# project.net
KiCad netlist of a schematic drawn in Altium Designer
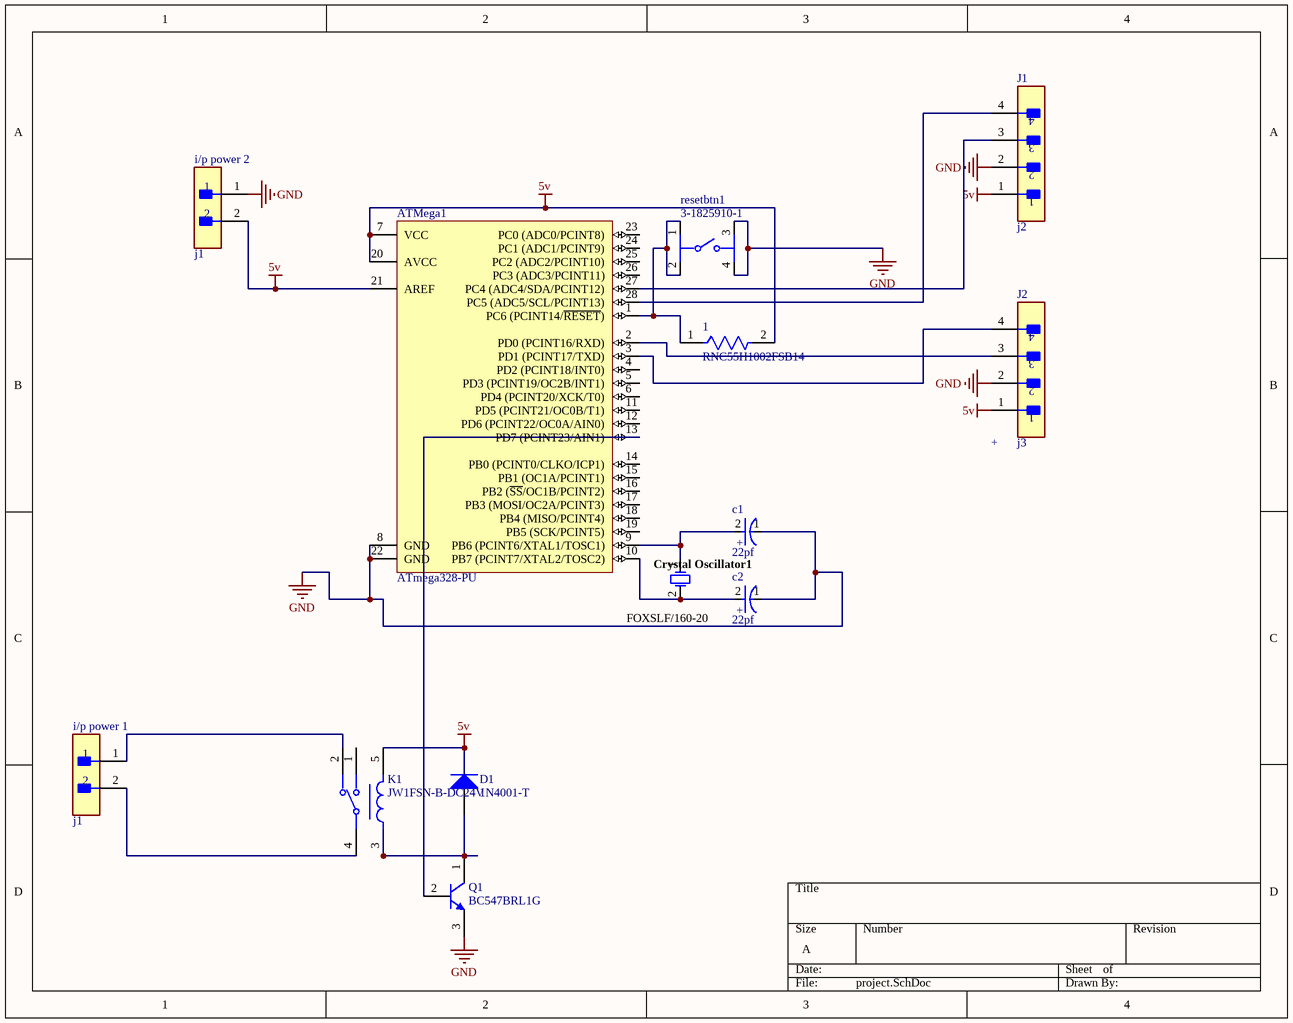
[diagram p0: project.SchDoc]

(export (version "E")
  (design (tool "Eeschema 10.0.6"))
  (components
    (comp (ref "1")
      (value "RNC55H1002FSB14")
      (footprint "FP-RNC55-MFG")
      (description "RES 10K OHM 1/8W 1% AXIAL")
      (fields
        (field (name "TOLERANCE") "1%")
        (field (name "OCTOPART") "https://octopart.com/rnc55h1002fs-vishay-40848808")
      )
      (libsource (lib "Altium Content Vault") (part "1029c3af85768c4190bb7ad29bc67b5"))
    )
    (comp (ref "ATMega1")
      (value "ATmega328-PU")
      (footprint "28P3")
      (libsource (lib "Altium Content Vault") (part "MC-8B-ATM48-IL28"))
    )
    (comp (ref "c1")
      (value "22pf")
      (footprint "FP-RAD-TH-D_10_0_5-L_20_2-MFG")
      (description "Aluminum Electrolytic Capacitors (Radial Lead Type) 10uF ±20% 400V")
      (fields (field (name "TOLERANCE") "20%") (field (name "VOLTAGE") "400V"))
      (libsource (lib "Altium Content Vault") (part "203bc49f2ac43e59fd269a8c329ed05"))
    )
    (comp (ref "c2")
      (value "22pf")
      (footprint "FP-RAD-TH-D_10_0_5-L_20_2-MFG")
      (description "Aluminum Electrolytic Capacitors (Radial Lead Type) 10uF ±20% 400V")
      (fields (field (name "TOLERANCE") "20%") (field (name "VOLTAGE") "400V"))
      (libsource (lib "Altium Content Vault") (part "203bc49f2ac43e59fd269a8c329ed05"))
    )
    (comp (ref "Crystal Oscillator1")
      (value "FOXSLF/160-20")
      (footprint "FOX-FOXSLF160-20")
      (description "Resistance Weld Thru-Hole Crystal, 16 MHz, -20 to 70 degC, 2-Pin THD, RoHS, Bulk")
      (fields (field (name "TOLERANCE") "1%"))
      (libsource (lib "Altium Content Vault") (part "XTAL-1-2-2"))
    )
    (comp (ref "D1")
      (value "1N4001-T")
      (footprint "DIOD-DO-41-P-2_V")
      (description "1.0 A Rectifier, 15 pF, 50 V, -65 to 150 degC, 2-Pin DO-41 Plastic, RoHS, Tape and Reel")
      (fields (field (name "MANUFACTURER") "Diodes Inc"))
      (libsource (lib "Altium Content Vault") (part "DIOD-D-A1K2-2"))
    )
    (comp (ref "i/p power 1")
      (value "j1")
      (footprint "FP-22-04-1021-MFG")
      (description "CONN HEADER VERT 2POS 2.5MM")
      (libsource (lib "Altium Content Vault") (part "3bc925449376181038e59eaffc5286c"))
    )
    (comp (ref "i/p power 2")
      (value "j1")
      (footprint "FP-22-04-1021-MFG")
      (description "CONN HEADER VERT 2POS 2.5MM")
      (libsource (lib "Altium Content Vault") (part "3bc925449376181038e59eaffc5286c"))
    )
    (comp (ref "J1")
      (value "j2")
      (footprint "FP-47053-3000-MFG")
      (description "CONN HEADER VERT 4POS 2.54MM")
      (libsource (lib "Altium Content Vault") (part "299a8cea1bdcbc3624fe62c390fa72c"))
    )
    (comp (ref "J2")
      (value "j3")
      (footprint "FP-47053-3000-MFG")
      (description "CONN HEADER VERT 4POS 2.54MM")
      (libsource (lib "Altium Content Vault") (part "299a8cea1bdcbc3624fe62c390fa72c"))
    )
    (comp (ref "K1")
      (value "JW1FSN-B-DC24V")
      (footprint "FP-JW1FSN-B-DC24V-MFG")
      (description "RELAY GEN PURPOSE SPDT 10A 24V")
      (libsource (lib "Altium Content Vault") (part "9326bfaabe3e5fa933881ff237cda8c"))
    )
    (comp (ref "Q1")
      (value "BC547BRL1G")
      (footprint "ONSC-TO-92-3-29-11_AM_BL")
      (description "Amplifier Transistor, NPN Silicon, 3-Pin TO-92, Pb-Free, Tape and Reel")
      (fields (field (name "MANUFACTURER") "On Semiconductor"))
      (libsource (lib "Altium Content Vault") (part "ONSC-NPN-C1B2E3-3"))
    )
    (comp (ref "resetbtn1")
      (value "3-1825910-1")
      (footprint "FP-3-1825910-1-MFG")
      (description "SWITCH TACTILE SPST-NO 0.05A 24V")
      (fields
        (field (name "MANUFACTURER") "TE Connectivity")
        (field (name "OCTOPART") "https://octopart.com/3-1825910-1-te+connectivity-46506874")
      )
      (libsource (lib "Altium Content Vault") (part "b8895f3f4cefb76e1819d2863dba89b"))
    )
  )
  (nets
    (net (code "1") (name "5v") (class "Default")
      (node (ref "1") (pin "2") (pinfunction "2_2") (pintype "passive"))
      (node (ref "ATMega1") (pin "20") (pinfunction "AVCC_20") (pintype "power_in"))
      (node (ref "ATMega1") (pin "21") (pinfunction "AREF_21") (pintype "power_in"))
      (node (ref "ATMega1") (pin "7") (pinfunction "VCC_7") (pintype "power_in"))
      (node (ref "D1") (pin "2") (pinfunction "K_2") (pintype "passive"))
      (node (ref "J1") (pin "1") (pinfunction "1_1") (pintype "passive"))
      (node (ref "J2") (pin "1") (pinfunction "1_1") (pintype "passive"))
      (node (ref "K1") (pin "5") (pinfunction "5_5") (pintype "passive"))
      (node (ref "i/p power 2") (pin "2") (pinfunction "2_2") (pintype "passive"))
    )
    (net (code "2") (name "GND") (class "Default")
      (node (ref "ATMega1") (pin "22") (pinfunction "GND_22") (pintype "power_in"))
      (node (ref "ATMega1") (pin "8") (pinfunction "GND_8") (pintype "power_in"))
      (node (ref "J1") (pin "2") (pinfunction "2_2") (pintype "passive"))
      (node (ref "J2") (pin "2") (pinfunction "2_2") (pintype "passive"))
      (node (ref "Q1") (pin "3") (pinfunction "E_3") (pintype "passive"))
      (node (ref "c1") (pin "1") (pinfunction "C_1") (pintype "passive"))
      (node (ref "c2") (pin "1") (pinfunction "C_1") (pintype "passive"))
      (node (ref "i/p power 2") (pin "1") (pinfunction "1_1") (pintype "passive"))
      (node (ref "resetbtn1") (pin "3") (pinfunction "3_3") (pintype "passive"))
      (node (ref "resetbtn1") (pin "4") (pinfunction "4_4") (pintype "passive"))
    )
    (net (code "3") (name "Net-(ATMega1-PB6_(PCINT6{slash}XTAL1{slash}TOSC1))") (class "Default")
      (node (ref "ATMega1") (pin "9") (pinfunction "PB6_(PCINT6/XTAL1/TOSC1)_9") (pintype "bidirectional"))
      (node (ref "Crystal Oscillator1") (pin "1") (pinfunction "1_1") (pintype "passive"))
      (node (ref "c1") (pin "2") (pinfunction "A_2") (pintype "passive"))
    )
    (net (code "4") (name "Net-(ATMega1-PB7_(PCINT7{slash}XTAL2{slash}TOSC2))") (class "Default")
      (node (ref "ATMega1") (pin "10") (pinfunction "PB7_(PCINT7/XTAL2/TOSC2)_10") (pintype "bidirectional"))
      (node (ref "Crystal Oscillator1") (pin "2") (pinfunction "2_2") (pintype "passive"))
      (node (ref "c2") (pin "2") (pinfunction "A_2") (pintype "passive"))
    )
    (net (code "5") (name "Net-(ATMega1-PC4_(ADC4{slash}SDA{slash}PCINT12))") (class "Default")
      (node (ref "ATMega1") (pin "27") (pinfunction "PC4_(ADC4/SDA/PCINT12)_27") (pintype "bidirectional"))
      (node (ref "J1") (pin "3") (pinfunction "3_3") (pintype "passive"))
    )
    (net (code "6") (name "Net-(ATMega1-PC5_(ADC5{slash}SCL{slash}PCINT13))") (class "Default")
      (node (ref "ATMega1") (pin "28") (pinfunction "PC5_(ADC5/SCL/PCINT13)_28") (pintype "bidirectional"))
      (node (ref "J1") (pin "4") (pinfunction "4_4") (pintype "passive"))
    )
    (net (code "7") (name "Net-(ATMega1-PC6_(PCINT14{slash}~{RESET}))") (class "Default")
      (node (ref "1") (pin "1") (pinfunction "1_1") (pintype "passive"))
      (node (ref "ATMega1") (pin "1") (pinfunction "PC6_(PCINT14/~{RESET})_1") (pintype "bidirectional"))
      (node (ref "resetbtn1") (pin "1") (pinfunction "1_1") (pintype "passive"))
      (node (ref "resetbtn1") (pin "2") (pinfunction "2_2") (pintype "passive"))
    )
    (net (code "8") (name "Net-(ATMega1-PD0_(PCINT16{slash}RXD))") (class "Default")
      (node (ref "ATMega1") (pin "2") (pinfunction "PD0_(PCINT16/RXD)_2") (pintype "bidirectional"))
      (node (ref "J2") (pin "3") (pinfunction "3_3") (pintype "passive"))
    )
    (net (code "9") (name "Net-(ATMega1-PD1_(PCINT17{slash}TXD))") (class "Default")
      (node (ref "ATMega1") (pin "3") (pinfunction "PD1_(PCINT17/TXD)_3") (pintype "bidirectional"))
      (node (ref "J2") (pin "4") (pinfunction "4_4") (pintype "passive"))
    )
    (net (code "10") (name "Net-(ATMega1-PD7_(PCINT23{slash}AIN1))") (class "Default")
      (node (ref "ATMega1") (pin "13") (pinfunction "PD7_(PCINT23/AIN1)_13") (pintype "bidirectional"))
      (node (ref "Q1") (pin "2") (pinfunction "B_2") (pintype "passive"))
    )
    (net (code "11") (name "Net-(D1-A)") (class "Default")
      (node (ref "D1") (pin "1") (pinfunction "A_1") (pintype "passive"))
      (node (ref "K1") (pin "3") (pinfunction "3_3") (pintype "passive"))
      (node (ref "Q1") (pin "1") (pinfunction "C_1") (pintype "passive"))
    )
    (net (code "12") (name "Net-(K1-Pad2)") (class "Default")
      (node (ref "K1") (pin "2") (pinfunction "2_2") (pintype "passive"))
      (node (ref "i/p power 1") (pin "1") (pinfunction "1_1") (pintype "passive"))
    )
    (net (code "13") (name "Net-(K1-Pad4)") (class "Default")
      (node (ref "K1") (pin "4") (pinfunction "4_4") (pintype "passive"))
      (node (ref "i/p power 1") (pin "2") (pinfunction "2_2") (pintype "passive"))
    )
    (net (code "14") (name "unconnected-(ATMega1-PB0_(PCINT0{slash}CLKO{slash}ICP1)-Pad14)") (class "Default")
      (node (ref "ATMega1") (pin "14") (pinfunction "PB0_(PCINT0/CLKO/ICP1)_14") (pintype "bidirectional"))
    )
    (net (code "15") (name "unconnected-(ATMega1-PB1_(OC1A{slash}PCINT1)-Pad15)") (class "Default")
      (node (ref "ATMega1") (pin "15") (pinfunction "PB1_(OC1A/PCINT1)_15") (pintype "bidirectional"))
    )
    (net (code "16") (name "unconnected-(ATMega1-PB2_(~{SS}{slash}OC1B{slash}PCINT2)-Pad16)") (class "Default")
      (node (ref "ATMega1") (pin "16") (pinfunction "PB2_(~{SS}/OC1B/PCINT2)_16") (pintype "bidirectional"))
    )
    (net (code "17") (name "unconnected-(ATMega1-PB3_(MOSI{slash}OC2A{slash}PCINT3)-Pad17)") (class "Default")
      (node (ref "ATMega1") (pin "17") (pinfunction "PB3_(MOSI/OC2A/PCINT3)_17") (pintype "bidirectional"))
    )
    (net (code "18") (name "unconnected-(ATMega1-PB4_(MISO{slash}PCINT4)-Pad18)") (class "Default")
      (node (ref "ATMega1") (pin "18") (pinfunction "PB4_(MISO/PCINT4)_18") (pintype "bidirectional"))
    )
    (net (code "19") (name "unconnected-(ATMega1-PB5_(SCK{slash}PCINT5)-Pad19)") (class "Default")
      (node (ref "ATMega1") (pin "19") (pinfunction "PB5_(SCK/PCINT5)_19") (pintype "bidirectional"))
    )
    (net (code "20") (name "unconnected-(ATMega1-PC0_(ADC0{slash}PCINT8)-Pad23)") (class "Default")
      (node (ref "ATMega1") (pin "23") (pinfunction "PC0_(ADC0/PCINT8)_23") (pintype "bidirectional"))
    )
    (net (code "21") (name "unconnected-(ATMega1-PC1_(ADC1{slash}PCINT9)-Pad24)") (class "Default")
      (node (ref "ATMega1") (pin "24") (pinfunction "PC1_(ADC1/PCINT9)_24") (pintype "bidirectional"))
    )
    (net (code "22") (name "unconnected-(ATMega1-PC2_(ADC2{slash}PCINT10)-Pad25)") (class "Default")
      (node (ref "ATMega1") (pin "25") (pinfunction "PC2_(ADC2/PCINT10)_25") (pintype "bidirectional"))
    )
    (net (code "23") (name "unconnected-(ATMega1-PC3_(ADC3{slash}PCINT11)-Pad26)") (class "Default")
      (node (ref "ATMega1") (pin "26") (pinfunction "PC3_(ADC3/PCINT11)_26") (pintype "bidirectional"))
    )
    (net (code "24") (name "unconnected-(ATMega1-PD2_(PCINT18{slash}INT0)-Pad4)") (class "Default")
      (node (ref "ATMega1") (pin "4") (pinfunction "PD2_(PCINT18/INT0)_4") (pintype "bidirectional"))
    )
    (net (code "25") (name "unconnected-(ATMega1-PD3_(PCINT19{slash}OC2B{slash}INT1)-Pad5)") (class "Default")
      (node (ref "ATMega1") (pin "5") (pinfunction "PD3_(PCINT19/OC2B/INT1)_5") (pintype "bidirectional"))
    )
    (net (code "26") (name "unconnected-(ATMega1-PD4_(PCINT20{slash}XCK{slash}T0)-Pad6)") (class "Default")
      (node (ref "ATMega1") (pin "6") (pinfunction "PD4_(PCINT20/XCK/T0)_6") (pintype "bidirectional"))
    )
    (net (code "27") (name "unconnected-(ATMega1-PD5_(PCINT21{slash}OC0B{slash}T1)-Pad11)") (class "Default")
      (node (ref "ATMega1") (pin "11") (pinfunction "PD5_(PCINT21/OC0B/T1)_11") (pintype "bidirectional"))
    )
    (net (code "28") (name "unconnected-(ATMega1-PD6_(PCINT22{slash}OC0A{slash}AIN0)-Pad12)") (class "Default")
      (node (ref "ATMega1") (pin "12") (pinfunction "PD6_(PCINT22/OC0A/AIN0)_12") (pintype "bidirectional"))
    )
    (net (code "29") (name "unconnected-(K1-Pad1)") (class "Default")
      (node (ref "K1") (pin "1") (pinfunction "1_1") (pintype "passive"))
    )
  )
)
